# PM12_P5V5.net
KiCad netlist of a schematic drawn in Altium Designer
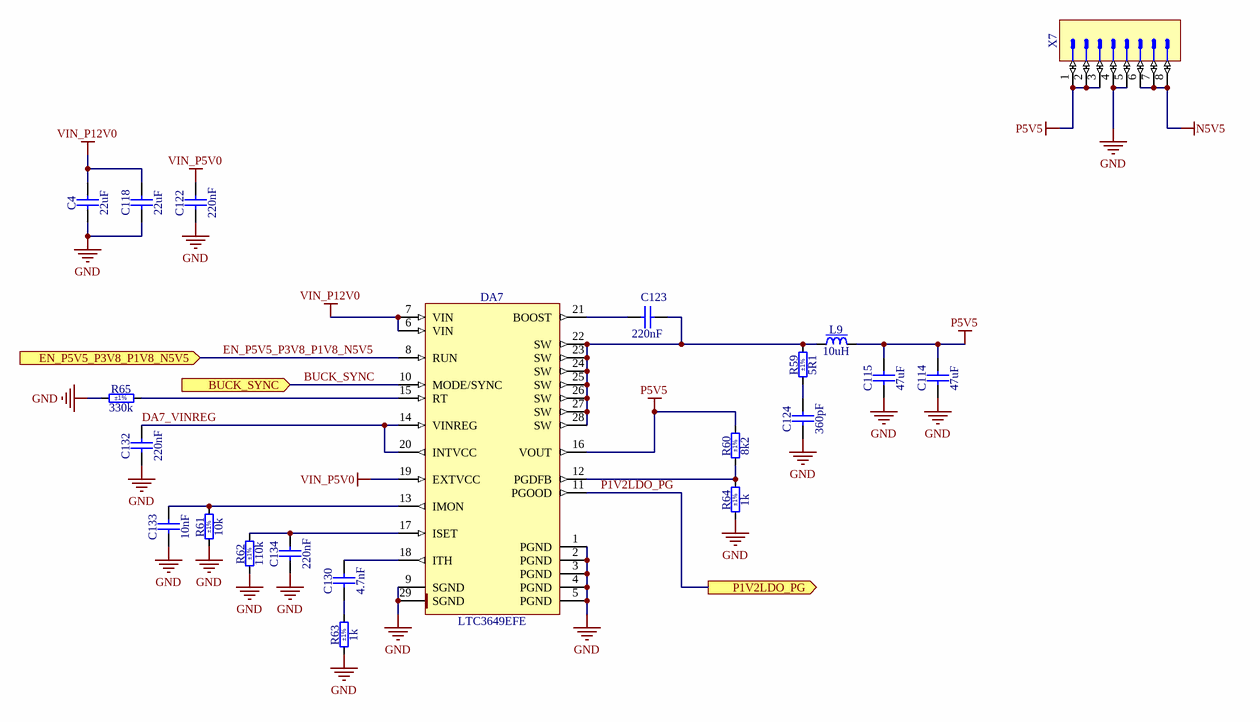
[diagram p0: PM12_P5V5.SchDoc]

(export (version "E")
  (design (tool "Eeschema 10.0.6"))
  (components
    (comp (ref "C4")
      (value "22uF")
      (footprint "CAPC3216X180N")
      (description "Non-polarised capacitor")
      (fields
        (field (name "PART NUMBER") "CC1206_22UF_25V_20%_X5R")
        (field (name "VOLTAGE") "25V")
        (field (name "AUTHOR") "CERN DEM WB")
      )
      (libsource (lib "Capacitors") (part "Capacitor - non polarized"))
    )
    (comp (ref "C114")
      (value "47uF")
      (footprint "CAPC3225X270N")
      (description "Non-polarised capacitor")
      (fields
        (field (name "PART NUMBER") "CC1210_47UF_16V_20%_X5R")
        (field (name "VOLTAGE") "16V")
        (field (name "AUTHOR") "CERN DEM MR")
      )
      (libsource (lib "Capacitors") (part "Capacitor - non polarized"))
    )
    (comp (ref "C115")
      (value "47uF")
      (footprint "CAPC3225X270N")
      (description "Non-polarised capacitor")
      (fields
        (field (name "PART NUMBER") "CC1210_47UF_16V_20%_X5R")
        (field (name "VOLTAGE") "16V")
        (field (name "AUTHOR") "CERN DEM MR")
      )
      (libsource (lib "Capacitors") (part "Capacitor - non polarized"))
    )
    (comp (ref "C118")
      (value "22uF")
      (footprint "CAPC3216X180N")
      (description "Non-polarised capacitor")
      (fields
        (field (name "PART NUMBER") "CC1206_22UF_25V_20%_X5R")
        (field (name "VOLTAGE") "25V")
        (field (name "AUTHOR") "CERN DEM WB")
      )
      (libsource (lib "Capacitors") (part "Capacitor - non polarized"))
    )
    (comp (ref "C122")
      (value "220nF")
      (footprint "CAPC2012X135N")
      (description "Non-polarised capacitor")
      (fields
        (field (name "PART NUMBER") "CC0805_220NF_50V_10%_X7R")
        (field (name "VOLTAGE") "50V")
        (field (name "AUTHOR") "CERN DEM JLC")
      )
      (libsource (lib "Capacitors") (part "Capacitor - non polarized"))
    )
    (comp (ref "C123")
      (value "220nF")
      (footprint "CAPC2012X135N")
      (description "Non-polarised capacitor")
      (fields
        (field (name "PART NUMBER") "CC0805_220NF_50V_10%_X7R")
        (field (name "VOLTAGE") "50V")
        (field (name "AUTHOR") "CERN DEM JLC")
      )
      (libsource (lib "Capacitors") (part "Capacitor - non polarized"))
    )
    (comp (ref "C124")
      (value "360pF")
      (footprint "CAPC2013X145N")
      (description "Non-polarised capacitor")
      (fields
        (field (name "PART NUMBER") "CC0805_360PF_50V_5%_C0G")
        (field (name "VOLTAGE") "50V")
        (field (name "AUTHOR") "CERN DEM HF")
      )
      (libsource (lib "Capacitors") (part "Capacitor - non polarized"))
    )
    (comp (ref "C130")
      (value "4.7nF")
      (footprint "CAPC2012X135N")
      (description "Non-polarised capacitor")
      (fields
        (field (name "PART NUMBER") "CC0805_4.7NF_50V_10%_X7R")
        (field (name "VOLTAGE") "50V")
        (field (name "AUTHOR") "CERN DEM JLC")
      )
      (libsource (lib "Capacitors") (part "Capacitor - non polarized"))
    )
    (comp (ref "C132")
      (value "220nF")
      (footprint "CAPC2012X135N")
      (description "Non-polarised capacitor")
      (fields
        (field (name "PART NUMBER") "CC0805_220NF_50V_10%_X7R")
        (field (name "VOLTAGE") "50V")
        (field (name "AUTHOR") "CERN DEM JLC")
      )
      (libsource (lib "Capacitors") (part "Capacitor - non polarized"))
    )
    (comp (ref "C133")
      (value "10nF")
      (footprint "CAPC2012X135N")
      (description "Non-polarised capacitor")
      (fields
        (field (name "PART NUMBER") "CC0805_10NF_50V_10%_X7R")
        (field (name "VOLTAGE") "50V")
        (field (name "AUTHOR") "CERN DEM JLC")
      )
      (libsource (lib "Capacitors") (part "Capacitor - non polarized"))
    )
    (comp (ref "C134")
      (value "220nF")
      (footprint "CAPC2012X135N")
      (description "Non-polarised capacitor")
      (fields
        (field (name "PART NUMBER") "CC0805_220NF_50V_10%_X7R")
        (field (name "VOLTAGE") "50V")
        (field (name "AUTHOR") "CERN DEM JLC")
      )
      (libsource (lib "Capacitors") (part "Capacitor - non polarized"))
    )
    (comp (ref "DA7")
      (value "LTC3649EFE")
      (footprint "SOP65P640X120-29N-R274X475")
      (description "60V, 4A Synchronous Step-Down Regulator with Rail-to-Rail Programmable Output")
      (fields (field (name "MANUFACTURER") "LINEAR TECHNOLOGY") (field (name "AUTHOR") "CERN DEM HF"))
      (libsource (lib "ICs And Semiconductors") (part "LTC3649XFE"))
    )
    (comp (ref "L9")
      (value "10uH")
      (footprint "IND_VISHAY_IHPL4040DZ-01")
      (description "Inductor With Core")
      (fields
        (field (name "PART NUMBER") "IND4040_10UH_20%_VISHAY_IHLP-4040DZ-01")
        (field (name "POWER") "6.8A")
        (field (name "AUTHOR") "CERN DEM HF")
      )
      (libsource (lib "Inductors & Transformers") (part "Inductor With Magnetic core"))
    )
    (comp (ref "R59")
      (value "5R1")
      (footprint "RESC2012X60N")
      (description "Resistor - 1%")
      (fields
        (field (name "TOLERANCE") "±1%")
        (field (name "PART NUMBER") "R0805_5R1_1%_0.125W_100PPM")
        (field (name "POWER") "0.125W")
        (field (name "AUTHOR") "CERN DEM HF")
      )
      (libsource (lib "Resistors") (part "Resistor - 1%"))
    )
    (comp (ref "R60")
      (value "8k2")
      (footprint "RESC2012X60N")
      (description "Resistor - 1%")
      (fields
        (field (name "TOLERANCE") "±1%")
        (field (name "PART NUMBER") "R0805_8K2_1%_0.125W_100PPM")
        (field (name "POWER") "0.125W")
        (field (name "AUTHOR") "CERN DEM JLC")
      )
      (libsource (lib "Resistors") (part "Resistor - 1%"))
    )
    (comp (ref "R61")
      (value "10k")
      (footprint "RESC2012X60N")
      (description "Resistor - 1%")
      (fields
        (field (name "TOLERANCE") "±1%")
        (field (name "PART NUMBER") "R0805_10K_1%_0.125W_100PPM")
        (field (name "POWER") "0.125W")
        (field (name "AUTHOR") "CERN DEM JLC")
      )
      (libsource (lib "Resistors") (part "Resistor - 1%"))
    )
    (comp (ref "R62")
      (value "110k")
      (footprint "RESC2012X60N")
      (description "Resistor - 1%")
      (fields
        (field (name "TOLERANCE") "±1%")
        (field (name "PART NUMBER") "R0805_110K_1%_0.125W_100PPM")
        (field (name "POWER") "0.125W")
        (field (name "AUTHOR") "CERN DEM JLC")
      )
      (libsource (lib "Resistors") (part "Resistor - 1%"))
    )
    (comp (ref "R63")
      (value "1k")
      (footprint "RESC2012X60N")
      (description "Resistor - 1%")
      (fields
        (field (name "TOLERANCE") "±1%")
        (field (name "PART NUMBER") "R0805_1K_1%_0.125W_100PPM")
        (field (name "POWER") "0.125W")
        (field (name "AUTHOR") "CERN DEM JLC")
      )
      (libsource (lib "Resistors") (part "Resistor - 1%"))
    )
    (comp (ref "R64")
      (value "1k")
      (footprint "RESC2012X60N")
      (description "Resistor - 1%")
      (fields
        (field (name "TOLERANCE") "±1%")
        (field (name "PART NUMBER") "R0805_1K_1%_0.125W_100PPM")
        (field (name "POWER") "0.125W")
        (field (name "AUTHOR") "CERN DEM JLC")
      )
      (libsource (lib "Resistors") (part "Resistor - 1%"))
    )
    (comp (ref "R65")
      (value "330k")
      (footprint "RESC2012X60N")
      (description "Resistor - 1%")
      (fields
        (field (name "TOLERANCE") "±1%")
        (field (name "PART NUMBER") "R0805_330K_1%_0.125W_100PPM")
        (field (name "POWER") "0.125W")
        (field (name "AUTHOR") "CERN DEM JLC")
      )
      (libsource (lib "Resistors") (part "Resistor - 1%"))
    )
    (comp (ref "X7")
      (value "Header 8")
      (footprint "SAMTEC_DW-08-09-L-S-470")
      (description "Connector 8 Male")
      (fields
        (field (name "PART NUMBER") "SAMTEC_DW-08-09-L-S-470")
        (field (name "MANUFACTURER") "SAMTEC")
        (field (name "AUTHOR") "CERN DEM HF")
      )
      (libsource (lib "Connectors") (part "Connector 8 Male"))
    )
  )
  (nets
    (net (code "1") (name "/BUCK_SYNC") (class "Default")
      (node (ref "DA7") (pin "10") (pinfunction "MODE/SYNC_10") (pintype "input"))
    )
    (net (code "2") (name "/DA7_VINREG") (class "Default")
      (node (ref "C132") (pin "2") (pinfunction "2_2") (pintype "passive"))
      (node (ref "DA7") (pin "14") (pinfunction "VINREG_14") (pintype "input"))
      (node (ref "DA7") (pin "20") (pinfunction "INTVCC_20") (pintype "output"))
    )
    (net (code "3") (name "/EN_P5V5_P3V8_P1V8_N5V5") (class "Default")
      (node (ref "DA7") (pin "8") (pinfunction "RUN_8") (pintype "input"))
    )
    (net (code "4") (name "/P1V2LDO_PG") (class "Default")
      (node (ref "DA7") (pin "11") (pinfunction "PGOOD_11") (pintype "output"))
    )
    (net (code "5") (name "GND") (class "Default")
      (node (ref "C114") (pin "1") (pinfunction "1_1") (pintype "passive"))
      (node (ref "C115") (pin "1") (pinfunction "1_1") (pintype "passive"))
      (node (ref "C118") (pin "1") (pinfunction "1_1") (pintype "passive"))
      (node (ref "C122") (pin "1") (pinfunction "1_1") (pintype "passive"))
      (node (ref "C124") (pin "1") (pinfunction "1_1") (pintype "passive"))
      (node (ref "C132") (pin "1") (pinfunction "1_1") (pintype "passive"))
      (node (ref "C133") (pin "1") (pinfunction "1_1") (pintype "passive"))
      (node (ref "C134") (pin "1") (pinfunction "1_1") (pintype "passive"))
      (node (ref "C4") (pin "1") (pinfunction "1_1") (pintype "passive"))
      (node (ref "DA7") (pin "1") (pinfunction "PGND_1") (pintype "power_in"))
      (node (ref "DA7") (pin "2") (pinfunction "PGND_2") (pintype "power_in"))
      (node (ref "DA7") (pin "29") (pinfunction "SGND_29") (pintype "power_in"))
      (node (ref "DA7") (pin "3") (pinfunction "PGND_3") (pintype "power_in"))
      (node (ref "DA7") (pin "4") (pinfunction "PGND_4") (pintype "power_in"))
      (node (ref "DA7") (pin "5") (pinfunction "PGND_5") (pintype "power_in"))
      (node (ref "DA7") (pin "9") (pinfunction "SGND_9") (pintype "power_in"))
      (node (ref "R61") (pin "1") (pinfunction "1_1") (pintype "passive"))
      (node (ref "R62") (pin "1") (pinfunction "1_1") (pintype "passive"))
      (node (ref "R63") (pin "1") (pinfunction "1_1") (pintype "passive"))
      (node (ref "R64") (pin "1") (pinfunction "1_1") (pintype "passive"))
      (node (ref "R65") (pin "1") (pinfunction "1_1") (pintype "passive"))
      (node (ref "X7") (pin "4") (pinfunction "4_4") (pintype "bidirectional"))
      (node (ref "X7") (pin "5") (pinfunction "5_5") (pintype "bidirectional"))
    )
    (net (code "6") (name "N5V5") (class "Default")
      (node (ref "X7") (pin "6") (pinfunction "6_6") (pintype "bidirectional"))
      (node (ref "X7") (pin "7") (pinfunction "7_7") (pintype "bidirectional"))
      (node (ref "X7") (pin "8") (pinfunction "8_8") (pintype "bidirectional"))
    )
    (net (code "7") (name "Net-(C123-Pad2)") (class "Default")
      (node (ref "C123") (pin "2") (pinfunction "2_2") (pintype "passive"))
      (node (ref "DA7") (pin "22") (pinfunction "SW_22") (pintype "output"))
      (node (ref "DA7") (pin "23") (pinfunction "SW_23") (pintype "output"))
      (node (ref "DA7") (pin "24") (pinfunction "SW_24") (pintype "output"))
      (node (ref "DA7") (pin "25") (pinfunction "SW_25") (pintype "output"))
      (node (ref "DA7") (pin "26") (pinfunction "SW_26") (pintype "output"))
      (node (ref "DA7") (pin "27") (pinfunction "SW_27") (pintype "output"))
      (node (ref "DA7") (pin "28") (pinfunction "SW_28") (pintype "output"))
      (node (ref "L9") (pin "1") (pinfunction "1_1") (pintype "passive"))
      (node (ref "R59") (pin "2") (pinfunction "2_2") (pintype "passive"))
    )
    (net (code "8") (name "Net-(C124-Pad2)") (class "Default")
      (node (ref "C124") (pin "2") (pinfunction "2_2") (pintype "passive"))
      (node (ref "R59") (pin "1") (pinfunction "1_1") (pintype "passive"))
    )
    (net (code "9") (name "Net-(C130-Pad1)") (class "Default")
      (node (ref "C130") (pin "1") (pinfunction "1_1") (pintype "passive"))
      (node (ref "R63") (pin "2") (pinfunction "2_2") (pintype "passive"))
    )
    (net (code "10") (name "Net-(DA7-BOOST)") (class "Default")
      (node (ref "C123") (pin "1") (pinfunction "1_1") (pintype "passive"))
      (node (ref "DA7") (pin "21") (pinfunction "BOOST_21") (pintype "output"))
    )
    (net (code "11") (name "Net-(DA7-IMON)") (class "Default")
      (node (ref "C133") (pin "2") (pinfunction "2_2") (pintype "passive"))
      (node (ref "DA7") (pin "13") (pinfunction "IMON_13") (pintype "output"))
      (node (ref "R61") (pin "2") (pinfunction "2_2") (pintype "passive"))
    )
    (net (code "12") (name "Net-(DA7-ISET)") (class "Default")
      (node (ref "C134") (pin "2") (pinfunction "2_2") (pintype "passive"))
      (node (ref "DA7") (pin "17") (pinfunction "ISET_17") (pintype "input"))
      (node (ref "R62") (pin "2") (pinfunction "2_2") (pintype "passive"))
    )
    (net (code "13") (name "Net-(DA7-ITH)") (class "Default")
      (node (ref "C130") (pin "2") (pinfunction "2_2") (pintype "passive"))
      (node (ref "DA7") (pin "18") (pinfunction "ITH_18") (pintype "output"))
    )
    (net (code "14") (name "Net-(DA7-PGDFB)") (class "Default")
      (node (ref "DA7") (pin "12") (pinfunction "PGDFB_12") (pintype "output"))
      (node (ref "R60") (pin "1") (pinfunction "1_1") (pintype "passive"))
      (node (ref "R64") (pin "2") (pinfunction "2_2") (pintype "passive"))
    )
    (net (code "15") (name "Net-(DA7-RT)") (class "Default")
      (node (ref "DA7") (pin "15") (pinfunction "RT_15") (pintype "input"))
      (node (ref "R65") (pin "2") (pinfunction "2_2") (pintype "passive"))
    )
    (net (code "16") (name "P5V5") (class "Default")
      (node (ref "C114") (pin "2") (pinfunction "2_2") (pintype "passive"))
      (node (ref "C115") (pin "2") (pinfunction "2_2") (pintype "passive"))
      (node (ref "DA7") (pin "16") (pinfunction "VOUT_16") (pintype "output"))
      (node (ref "L9") (pin "2") (pinfunction "2_2") (pintype "passive"))
      (node (ref "R60") (pin "2") (pinfunction "2_2") (pintype "passive"))
      (node (ref "X7") (pin "1") (pinfunction "1_1") (pintype "bidirectional"))
      (node (ref "X7") (pin "2") (pinfunction "2_2") (pintype "bidirectional"))
      (node (ref "X7") (pin "3") (pinfunction "3_3") (pintype "bidirectional"))
    )
    (net (code "17") (name "VIN_P5V0") (class "Default")
      (node (ref "C122") (pin "2") (pinfunction "2_2") (pintype "passive"))
      (node (ref "DA7") (pin "19") (pinfunction "EXTVCC_19") (pintype "input"))
    )
    (net (code "18") (name "VIN_P12V0") (class "Default")
      (node (ref "C118") (pin "2") (pinfunction "2_2") (pintype "passive"))
      (node (ref "C4") (pin "2") (pinfunction "2_2") (pintype "passive"))
      (node (ref "DA7") (pin "6") (pinfunction "VIN_6") (pintype "input"))
      (node (ref "DA7") (pin "7") (pinfunction "VIN_7") (pintype "input"))
    )
  )
)
